# Moneybox.net
KiCad netlist of a schematic drawn in Altium Designer
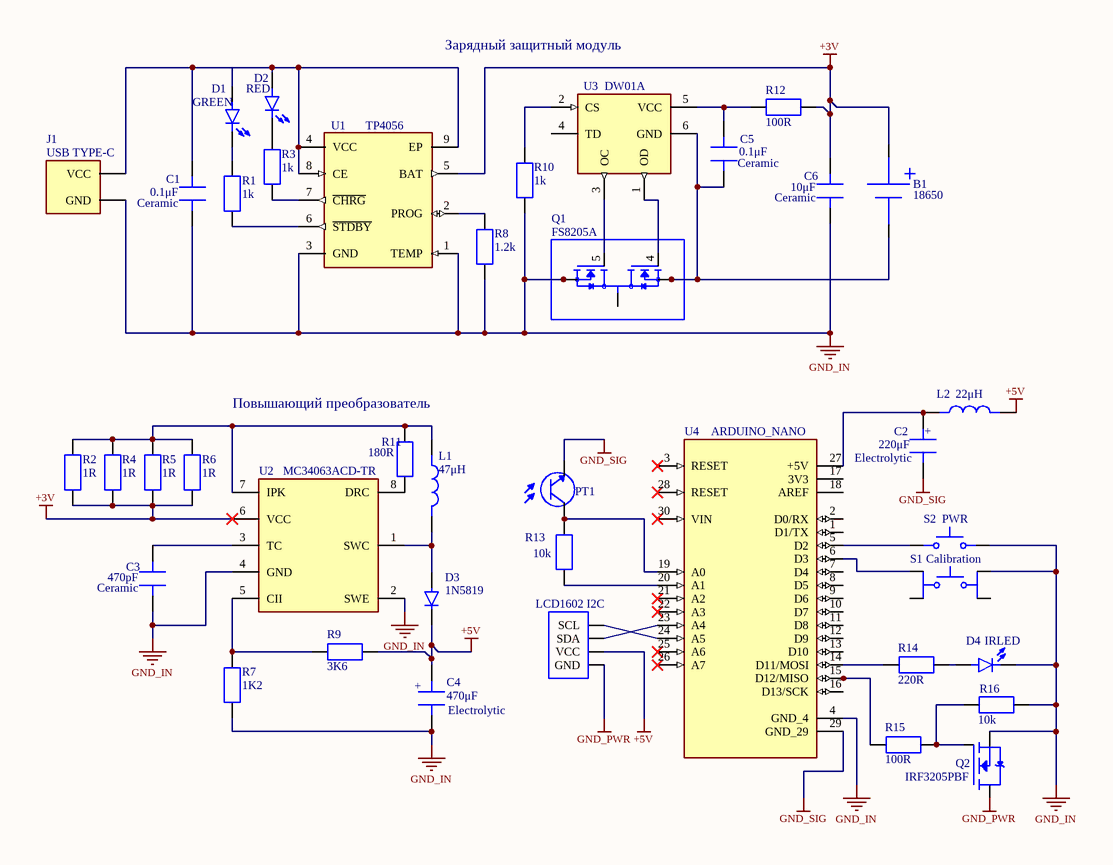
[diagram p0: Moneybox.SchDoc]

(export (version "E")
  (design (tool "Eeschema 10.0.6"))
  (components
    (comp (ref "B1") (value "18650") (footprint "18650 PLS 2") (libsource (lib "My") (part "Baterry 18650")))
    (comp (ref "C1")
      (value "0.1μF")
      (footprint "R1206")
      (fields (field (name "TYPES") "Ceramic") (field (name "Comment") "Capicator"))
      (libsource (lib "My") (part "Capicator"))
    )
    (comp (ref "C2")
      (value "220μF")
      (footprint "CAPICATOR Radial 6.3mm")
      (fields
        (field (name "POLARITY") "+")
        (field (name "TYPES") "Electrolytic")
        (field (name "Comment") "Capicator")
      )
      (libsource (lib "My") (part "Capicator"))
    )
    (comp (ref "C3")
      (value "470pF")
      (footprint "R1206")
      (fields (field (name "TYPES") "Ceramic") (field (name "Comment") "Capicator"))
      (libsource (lib "My") (part "Capicator"))
    )
    (comp (ref "C4")
      (value "470μF")
      (footprint "CAPICATOR Radial 6.3mm")
      (fields
        (field (name "POLARITY") "+")
        (field (name "TYPES") "Electrolytic")
        (field (name "Comment") "Capicator")
      )
      (libsource (lib "My") (part "Capicator"))
    )
    (comp (ref "C5")
      (value "0.1μF")
      (footprint "R1206")
      (fields (field (name "TYPES") "Ceramic") (field (name "Comment") "Capicator"))
      (libsource (lib "My") (part "Capicator"))
    )
    (comp (ref "C6")
      (value "10μF")
      (footprint "R1206")
      (fields (field (name "TYPES") "Ceramic") (field (name "Comment") "Capicator"))
      (libsource (lib "My") (part "Capicator"))
    )
    (comp (ref "D1")
      (value "GREEN")
      (footprint "LED_DIP")
      (description "infrared LED 850nm")
      (fields (field (name "MP") "WP7113ID") (field (name "MF") "Kingbright"))
      (libsource (lib "My") (part "IRLED"))
    )
    (comp (ref "D2")
      (value "RED")
      (footprint "LED_DIP")
      (description "infrared LED 850nm")
      (fields (field (name "MP") "WP7113ID") (field (name "MF") "Kingbright"))
      (libsource (lib "My") (part "IRLED"))
    )
    (comp (ref "D3")
      (value "1N5819")
      (footprint "DIOD 1N5819")
      (description "1A, 40V, Planar Schottky")
      (fields (field (name "MF") "Taiwan Semiconductor"))
      (libsource (lib "My") (part "1N5819"))
    )
    (comp (ref "D4")
      (value "IRLED")
      (footprint "IRLED_DIP")
      (description "infrared LED 850nm")
      (fields (field (name "MP") "WP7113ID") (field (name "MF") "Kingbright"))
      (libsource (lib "My") (part "IRLED"))
    )
    (comp (ref "J1")
      (value "USB Type C")
      (footprint "18650 PLS 2")
      (description "USB Type C, Power Only, Top mount, Center Height 1.68mm, Single Row, Surface Mount")
      (fields (field (name "MF") "Amphenol") (field (name "MP") "GSB1C411101DSHR"))
      (libsource (lib "My") (part "USB Type C"))
    )
    (comp (ref "L1")
      (value "47μH")
      (footprint "INDUCTOR THT")
      (description "Inductor THT axial")
      (fields (field (name "MF") "TDK Electronics") (field (name "MP") "B78108S1102K000"))
      (libsource (lib "My") (part "Inductor THT"))
    )
    (comp (ref "L2")
      (value "22μH")
      (footprint "INDUCTOR THT")
      (description "Inductor THT axial")
      (fields (field (name "MF") "TDK Electronics") (field (name "MP") "B78108S1102K000"))
      (libsource (lib "My") (part "Inductor THT"))
    )
    (comp (ref "LCD1") (value "LCD1602 I2C") (footprint "PLS-4") (libsource (lib "My") (part "LCD1602 I2C")))
    (comp (ref "PT1")
      (value "Phototransistors")
      (footprint "Phototransistors DIP")
      (description "Phototransistors 850nm Top View Radial")
      (fields (field (name "MF") "Vishay") (field (name "MP") "BPW85A"))
      (libsource (lib "My") (part "Phototransistors"))
    )
    (comp (ref "Q1")
      (value "FS8205A")
      (footprint "FS8205A")
      (fields (field (name "MF") "Fortune Semiconductor"))
      (libsource (lib "My") (part "FS8205A"))
    )
    (comp (ref "Q2")
      (value "IRF3205PBF")
      (footprint "MOSFET IRF3205PBF")
      (fields (field (name "MF") "Infineon Technologies"))
      (libsource (lib "My") (part "IRF3205PBF"))
    )
    (comp (ref "R1")
      (value "1k")
      (footprint "R1206")
      (fields (field (name "Comment") "Resistor 1206"))
      (libsource (lib "My") (part "R1206"))
    )
    (comp (ref "R2")
      (value "1R")
      (footprint "R1206")
      (fields (field (name "Comment") "Resistor 1206"))
      (libsource (lib "My") (part "R1206"))
    )
    (comp (ref "R3")
      (value "1k")
      (footprint "R1206")
      (fields (field (name "Comment") "Resistor 1206"))
      (libsource (lib "My") (part "R1206"))
    )
    (comp (ref "R4")
      (value "1R")
      (footprint "R1206")
      (fields (field (name "Comment") "Resistor 1206"))
      (libsource (lib "My") (part "R1206"))
    )
    (comp (ref "R5")
      (value "1R")
      (footprint "R1206")
      (fields (field (name "Comment") "Resistor 1206"))
      (libsource (lib "My") (part "R1206"))
    )
    (comp (ref "R6")
      (value "1R")
      (footprint "R1206")
      (fields (field (name "Comment") "Resistor 1206"))
      (libsource (lib "My") (part "R1206"))
    )
    (comp (ref "R7")
      (value "1K2")
      (footprint "R1206")
      (fields (field (name "Comment") "Resistor 1206"))
      (libsource (lib "My") (part "R1206"))
    )
    (comp (ref "R8")
      (value "1.2k")
      (footprint "R1206")
      (fields (field (name "Comment") "Resistor 1206"))
      (libsource (lib "My") (part "R1206"))
    )
    (comp (ref "R9")
      (value "3K6")
      (footprint "R1206")
      (fields (field (name "Comment") "Resistor 1206"))
      (libsource (lib "My") (part "R1206"))
    )
    (comp (ref "R10")
      (value "1k")
      (footprint "R1206")
      (fields (field (name "Comment") "Resistor 1206"))
      (libsource (lib "My") (part "R1206"))
    )
    (comp (ref "R11")
      (value "180R")
      (footprint "R1206")
      (fields (field (name "Comment") "Resistor 1206"))
      (libsource (lib "My") (part "R1206"))
    )
    (comp (ref "R12")
      (value "100R")
      (footprint "R1206")
      (fields (field (name "Comment") "Resistor 1206"))
      (libsource (lib "My") (part "R1206"))
    )
    (comp (ref "R13")
      (value "10k")
      (footprint "R1206")
      (fields (field (name "Comment") "Resistor 1206"))
      (libsource (lib "My") (part "R1206"))
    )
    (comp (ref "R14")
      (value "220R")
      (footprint "R1206")
      (fields (field (name "Comment") "Resistor 1206"))
      (libsource (lib "My") (part "R1206"))
    )
    (comp (ref "R15")
      (value "100R")
      (footprint "R1206")
      (fields (field (name "Comment") "Resistor 1206"))
      (libsource (lib "My") (part "R1206"))
    )
    (comp (ref "R16")
      (value "10k")
      (footprint "R1206")
      (fields (field (name "Comment") "Resistor 1206"))
      (libsource (lib "My") (part "R1206"))
    )
    (comp (ref "S1")
      (value "Сalibration")
      (footprint "Tactile Switch")
      (fields (field (name "MP") "TL1105AF160Q"))
      (libsource (lib "My") (part "Tactile Switch"))
    )
    (comp (ref "S2")
      (value "PWR")
      (footprint "PLS-2")
      (fields (field (name "MP") "TL1105AF160Q"))
      (libsource (lib "My") (part "Switch PLS-2"))
    )
    (comp (ref "U1")
      (value "TP4056")
      (footprint "TP4056")
      (description "Complete single cell Li-Ion battery with a constant current / constant voltage linear charger")
      (fields (field (name "MF") "NanJing Top Power ASIC Corp."))
      (libsource (lib "My") (part "TP4056"))
    )
    (comp (ref "U2")
      (value "MC34063ACD-TR")
      (footprint "MC34063ACD-TR_SOIC8")
      (fields (field (name "MF") "STMicroelectronics"))
      (libsource (lib "My") (part "MC34063ACD-TR"))
    )
    (comp (ref "U3")
      (value "DW01A")
      (footprint "DW01A")
      (description "One Cell Lithium-ion/Polymer Battery Protection IC")
      (fields (field (name "MF") "Fortune Semiconductor"))
      (libsource (lib "My") (part "DW01A"))
    )
    (comp (ref "U4")
      (value "ARDUINO_NANO")
      (footprint "ARDUINO_NANO")
      (description "ATmega328 Arduino Nano")
      (fields (field (name "MF") "Arduino") (field (name "MP") "Arduino Nano"))
      (libsource (lib "My") (part "ARDUINO_NANO"))
    )
  )
  (nets
    (net (code "1") (name "+3V") (class "Default")
      (node (ref "B1") (pin "1") (pinfunction "1_1") (pintype "passive"))
      (node (ref "C6") (pin "2") (pinfunction "2_2") (pintype "passive"))
      (node (ref "R12") (pin "2") (pinfunction "1_2") (pintype "passive"))
      (node (ref "R2") (pin "1") (pinfunction "0_1") (pintype "passive"))
      (node (ref "R4") (pin "1") (pinfunction "0_1") (pintype "passive"))
      (node (ref "R5") (pin "1") (pinfunction "0_1") (pintype "passive"))
      (node (ref "R6") (pin "1") (pinfunction "0_1") (pintype "passive"))
      (node (ref "U1") (pin "5") (pinfunction "BAT_5") (pintype "output"))
      (node (ref "U2") (pin "6") (pinfunction "VCC_6") (pintype "power_in"))
    )
    (net (code "2") (name "+5V") (class "Default")
      (node (ref "C4") (pin "1") (pinfunction "1_1") (pintype "passive"))
      (node (ref "D3") (pin "2") (pinfunction "2_2") (pintype "passive"))
      (node (ref "L2") (pin "2") (pinfunction "2_2") (pintype "passive"))
      (node (ref "LCD1") (pin "2") (pinfunction "VCC_2") (pintype "bidirectional"))
      (node (ref "R9") (pin "1") (pinfunction "0_1") (pintype "passive"))
    )
    (net (code "3") (name "GND_IN") (class "Default")
      (node (ref "C1") (pin "1") (pinfunction "1_1") (pintype "passive"))
      (node (ref "C3") (pin "1") (pinfunction "1_1") (pintype "passive"))
      (node (ref "C4") (pin "2") (pinfunction "2_2") (pintype "passive"))
      (node (ref "C6") (pin "1") (pinfunction "1_1") (pintype "passive"))
      (node (ref "D4") (pin "2") (pinfunction "2_2") (pintype "passive"))
      (node (ref "J1") (pin "2") (pinfunction "GND_2") (pintype "power_in"))
      (node (ref "Q1") (pin "6") (pinfunction "S2_6") (pintype "passive"))
      (node (ref "Q1") (pin "7") (pinfunction "S2_7") (pintype "passive"))
      (node (ref "Q2") (pin "3") (pinfunction "S_3") (pintype "passive"))
      (node (ref "R10") (pin "2") (pinfunction "1_2") (pintype "passive"))
      (node (ref "R16") (pin "2") (pinfunction "1_2") (pintype "passive"))
      (node (ref "R7") (pin "1") (pinfunction "0_1") (pintype "passive"))
      (node (ref "R8") (pin "2") (pinfunction "1_2") (pintype "passive"))
      (node (ref "S1") (pin "3") (pinfunction "3_3") (pintype "passive"))
      (node (ref "S2") (pin "2") (pinfunction "2_2") (pintype "passive"))
      (node (ref "U1") (pin "1") (pinfunction "TEMP_1") (pintype "input"))
      (node (ref "U1") (pin "3") (pinfunction "GND_3") (pintype "power_in"))
      (node (ref "U2") (pin "2") (pinfunction "SWE_2") (pintype "passive"))
      (node (ref "U2") (pin "4") (pinfunction "GND_4") (pintype "passive"))
      (node (ref "U4") (pin "4") (pinfunction "GND_4_4") (pintype "power_in"))
    )
    (net (code "4") (name "GND_PWR") (class "Default")
      (node (ref "LCD1") (pin "1") (pinfunction "GND_1") (pintype "bidirectional"))
      (node (ref "Q2") (pin "2") (pinfunction "D_2") (pintype "passive"))
    )
    (net (code "5") (name "GND_SIG") (class "Default")
      (node (ref "C2") (pin "2") (pinfunction "2_2") (pintype "passive"))
      (node (ref "PT1") (pin "2") (pinfunction "2_2") (pintype "passive"))
      (node (ref "U4") (pin "29") (pinfunction "GND_29_29") (pintype "power_in"))
    )
    (net (code "6") (name "Net-(J1-VCC)") (class "Default")
      (node (ref "C1") (pin "2") (pinfunction "2_2") (pintype "passive"))
      (node (ref "D1") (pin "1") (pinfunction "1_1") (pintype "passive"))
      (node (ref "D2") (pin "1") (pinfunction "1_1") (pintype "passive"))
      (node (ref "J1") (pin "1") (pinfunction "VCC_1") (pintype "power_in"))
      (node (ref "U1") (pin "4") (pinfunction "VCC_4") (pintype "power_in"))
      (node (ref "U1") (pin "8") (pinfunction "CE_8") (pintype "input"))
      (node (ref "U1") (pin "9") (pinfunction "EP_9") (pintype "passive"))
    )
    (net (code "7") (name "Net-(LCD1-SCL)") (class "Default")
      (node (ref "LCD1") (pin "4") (pinfunction "SCL_4") (pintype "bidirectional"))
      (node (ref "U4") (pin "24") (pinfunction "A5_24") (pintype "input"))
    )
    (net (code "8") (name "Net-(LCD1-SDA)") (class "Default")
      (node (ref "LCD1") (pin "3") (pinfunction "SDA_3") (pintype "bidirectional"))
      (node (ref "U4") (pin "23") (pinfunction "A4_23") (pintype "input"))
    )
    (net (code "9") (name "Net-(Q1-D12-Pad1)") (class "Default")
      (node (ref "Q1") (pin "1") (pinfunction "D12_1") (pintype "passive"))
      (node (ref "Q1") (pin "8") (pinfunction "D12_8") (pintype "passive"))
    )
    (net (code "10") (name "Net-(Q1-G1)") (class "Default")
      (node (ref "Q1") (pin "4") (pinfunction "G1_4") (pintype "passive"))
      (node (ref "U3") (pin "1") (pinfunction "OD_1") (pintype "output"))
    )
    (net (code "11") (name "Net-(Q1-G2)") (class "Default")
      (node (ref "Q1") (pin "5") (pinfunction "G2_5") (pintype "passive"))
      (node (ref "U3") (pin "3") (pinfunction "OC_3") (pintype "output"))
    )
    (net (code "12") (name "Net-(Q2-G)") (class "Default")
      (node (ref "Q2") (pin "1") (pinfunction "G_1") (pintype "passive"))
      (node (ref "R15") (pin "2") (pinfunction "1_2") (pintype "passive"))
      (node (ref "R16") (pin "1") (pinfunction "0_1") (pintype "passive"))
    )
    (net (code "13") (name "Net-(R1-0)") (class "Default")
      (node (ref "D1") (pin "2") (pinfunction "2_2") (pintype "passive"))
      (node (ref "R1") (pin "1") (pinfunction "0_1") (pintype "passive"))
    )
    (net (code "14") (name "Net-(R1-1)") (class "Default")
      (node (ref "R1") (pin "2") (pinfunction "1_2") (pintype "passive"))
      (node (ref "U1") (pin "6") (pinfunction "~{STDBY}_6") (pintype "output"))
    )
    (net (code "15") (name "Net-(R3-0)") (class "Default")
      (node (ref "D2") (pin "2") (pinfunction "2_2") (pintype "passive"))
      (node (ref "R3") (pin "1") (pinfunction "0_1") (pintype "passive"))
    )
    (net (code "16") (name "Net-(R3-1)") (class "Default")
      (node (ref "R3") (pin "2") (pinfunction "1_2") (pintype "passive"))
      (node (ref "U1") (pin "7") (pinfunction "~{CHRG}_7") (pintype "output"))
    )
    (net (code "17") (name "Net-(R7-1)") (class "Default")
      (node (ref "R7") (pin "2") (pinfunction "1_2") (pintype "passive"))
      (node (ref "R9") (pin "2") (pinfunction "1_2") (pintype "passive"))
      (node (ref "U2") (pin "5") (pinfunction "CII_5") (pintype "passive"))
    )
    (net (code "18") (name "Net-(R8-0)") (class "Default")
      (node (ref "R8") (pin "1") (pinfunction "0_1") (pintype "passive"))
      (node (ref "U1") (pin "2") (pinfunction "PROG_2") (pintype "bidirectional"))
    )
    (net (code "19") (name "Net-(R10-0)") (class "Default")
      (node (ref "R10") (pin "1") (pinfunction "0_1") (pintype "passive"))
      (node (ref "U3") (pin "2") (pinfunction "CS_2") (pintype "input"))
    )
    (net (code "20") (name "Net-(R11-0)") (class "Default")
      (node (ref "R11") (pin "1") (pinfunction "0_1") (pintype "passive"))
      (node (ref "U2") (pin "8") (pinfunction "DRC_8") (pintype "passive"))
    )
    (net (code "21") (name "Net-(R11-1)") (class "Default")
      (node (ref "L1") (pin "1") (pinfunction "1_1") (pintype "passive"))
      (node (ref "R11") (pin "2") (pinfunction "1_2") (pintype "passive"))
      (node (ref "R2") (pin "2") (pinfunction "1_2") (pintype "passive"))
      (node (ref "R4") (pin "2") (pinfunction "1_2") (pintype "passive"))
      (node (ref "R5") (pin "2") (pinfunction "1_2") (pintype "passive"))
      (node (ref "R6") (pin "2") (pinfunction "1_2") (pintype "passive"))
      (node (ref "U2") (pin "7") (pinfunction "IPK_7") (pintype "passive"))
    )
    (net (code "22") (name "Net-(R12-0)") (class "Default")
      (node (ref "C5") (pin "2") (pinfunction "2_2") (pintype "passive"))
      (node (ref "R12") (pin "1") (pinfunction "0_1") (pintype "passive"))
      (node (ref "U3") (pin "5") (pinfunction "VCC_5") (pintype "power_in"))
    )
    (net (code "23") (name "Net-(R13-0)") (class "Default")
      (node (ref "R13") (pin "1") (pinfunction "0_1") (pintype "passive"))
      (node (ref "U4") (pin "20") (pinfunction "A1_20") (pintype "input"))
    )
    (net (code "24") (name "Net-(R13-1)") (class "Default")
      (node (ref "PT1") (pin "1") (pinfunction "1_1") (pintype "passive"))
      (node (ref "R13") (pin "2") (pinfunction "1_2") (pintype "passive"))
      (node (ref "U4") (pin "19") (pinfunction "A0_19") (pintype "input"))
    )
    (net (code "25") (name "Net-(R14-0)") (class "Default")
      (node (ref "R14") (pin "1") (pinfunction "0_1") (pintype "passive"))
      (node (ref "U4") (pin "14") (pinfunction "D11/MOSI_14") (pintype "bidirectional"))
    )
    (net (code "26") (name "Net-(R14-1)") (class "Default")
      (node (ref "D4") (pin "1") (pinfunction "1_1") (pintype "passive"))
      (node (ref "R14") (pin "2") (pinfunction "1_2") (pintype "passive"))
    )
    (net (code "27") (name "Net-(R15-0)") (class "Default")
      (node (ref "R15") (pin "1") (pinfunction "0_1") (pintype "passive"))
      (node (ref "U4") (pin "15") (pinfunction "D12/MISO_15") (pintype "bidirectional"))
    )
    (net (code "28") (name "Net-(U2-SWC)") (class "Default")
      (node (ref "D3") (pin "1") (pinfunction "1_1") (pintype "passive"))
      (node (ref "L1") (pin "2") (pinfunction "2_2") (pintype "passive"))
      (node (ref "U2") (pin "1") (pinfunction "SWC_1") (pintype "passive"))
    )
    (net (code "29") (name "Net-(U2-TC)") (class "Default")
      (node (ref "C3") (pin "2") (pinfunction "2_2") (pintype "passive"))
      (node (ref "U2") (pin "3") (pinfunction "TC_3") (pintype "passive"))
    )
    (net (code "30") (name "Net-(U3-GND)") (class "Default")
      (node (ref "B1") (pin "2") (pinfunction "2_2") (pintype "passive"))
      (node (ref "C5") (pin "1") (pinfunction "1_1") (pintype "passive"))
      (node (ref "Q1") (pin "2") (pinfunction "S1_2") (pintype "passive"))
      (node (ref "Q1") (pin "3") (pinfunction "S1_3") (pintype "passive"))
      (node (ref "U3") (pin "6") (pinfunction "GND_6") (pintype "power_in"))
    )
    (net (code "31") (name "Net-(U4-+5V)") (class "Default")
      (node (ref "C2") (pin "1") (pinfunction "1_1") (pintype "passive"))
      (node (ref "L2") (pin "1") (pinfunction "1_1") (pintype "passive"))
      (node (ref "U4") (pin "27") (pinfunction "+5V_27") (pintype "power_in"))
    )
    (net (code "32") (name "Net-(U4-D2)") (class "Default")
      (node (ref "S2") (pin "1") (pinfunction "1_1") (pintype "passive"))
      (node (ref "U4") (pin "5") (pinfunction "D2_5") (pintype "bidirectional"))
    )
    (net (code "33") (name "Net-(U4-D3)") (class "Default")
      (node (ref "S1") (pin "1") (pinfunction "1_1") (pintype "passive"))
      (node (ref "U4") (pin "6") (pinfunction "D3_6") (pintype "bidirectional"))
    )
    (net (code "34") (name "unconnected-(S1-Pad2)") (class "Default")
      (node (ref "S1") (pin "2") (pinfunction "2_2") (pintype "passive"))
    )
    (net (code "35") (name "unconnected-(S1-Pad4)") (class "Default")
      (node (ref "S1") (pin "4") (pinfunction "4_4") (pintype "passive"))
    )
    (net (code "36") (name "unconnected-(U3-TD-Pad4)") (class "Default")
      (node (ref "U3") (pin "4") (pinfunction "TD_4") (pintype "passive"))
    )
    (net (code "37") (name "unconnected-(U4-3V3-Pad17)") (class "Default")
      (node (ref "U4") (pin "17") (pinfunction "3V3_17") (pintype "power_in"))
    )
    (net (code "38") (name "unconnected-(U4-A2-Pad21)") (class "Default")
      (node (ref "U4") (pin "21") (pinfunction "A2_21") (pintype "input+no_connect"))
    )
    (net (code "39") (name "unconnected-(U4-A3-Pad22)") (class "Default")
      (node (ref "U4") (pin "22") (pinfunction "A3_22") (pintype "input+no_connect"))
    )
    (net (code "40") (name "unconnected-(U4-A6-Pad25)") (class "Default")
      (node (ref "U4") (pin "25") (pinfunction "A6_25") (pintype "input+no_connect"))
    )
    (net (code "41") (name "unconnected-(U4-A7-Pad26)") (class "Default")
      (node (ref "U4") (pin "26") (pinfunction "A7_26") (pintype "input+no_connect"))
    )
    (net (code "42") (name "unconnected-(U4-AREF-Pad18)") (class "Default")
      (node (ref "U4") (pin "18") (pinfunction "AREF_18") (pintype "power_in"))
    )
    (net (code "43") (name "unconnected-(U4-D0{slash}RX-Pad2)") (class "Default")
      (node (ref "U4") (pin "2") (pinfunction "D0/RX_2") (pintype "bidirectional"))
    )
    (net (code "44") (name "unconnected-(U4-D1{slash}TX-Pad1)") (class "Default")
      (node (ref "U4") (pin "1") (pinfunction "D1/TX_1") (pintype "bidirectional"))
    )
    (net (code "45") (name "unconnected-(U4-D4-Pad7)") (class "Default")
      (node (ref "U4") (pin "7") (pinfunction "D4_7") (pintype "bidirectional"))
    )
    (net (code "46") (name "unconnected-(U4-D5-Pad8)") (class "Default")
      (node (ref "U4") (pin "8") (pinfunction "D5_8") (pintype "bidirectional"))
    )
    (net (code "47") (name "unconnected-(U4-D6-Pad9)") (class "Default")
      (node (ref "U4") (pin "9") (pinfunction "D6_9") (pintype "bidirectional"))
    )
    (net (code "48") (name "unconnected-(U4-D7-Pad10)") (class "Default")
      (node (ref "U4") (pin "10") (pinfunction "D7_10") (pintype "bidirectional"))
    )
    (net (code "49") (name "unconnected-(U4-D8-Pad11)") (class "Default")
      (node (ref "U4") (pin "11") (pinfunction "D8_11") (pintype "bidirectional"))
    )
    (net (code "50") (name "unconnected-(U4-D9-Pad12)") (class "Default")
      (node (ref "U4") (pin "12") (pinfunction "D9_12") (pintype "bidirectional"))
    )
    (net (code "51") (name "unconnected-(U4-D10-Pad13)") (class "Default")
      (node (ref "U4") (pin "13") (pinfunction "D10_13") (pintype "bidirectional"))
    )
    (net (code "52") (name "unconnected-(U4-D13{slash}SCK-Pad16)") (class "Default")
      (node (ref "U4") (pin "16") (pinfunction "D13/SCK_16") (pintype "bidirectional"))
    )
    (net (code "53") (name "unconnected-(U4-RESET-Pad3)") (class "Default")
      (node (ref "U4") (pin "3") (pinfunction "RESET_3") (pintype "input+no_connect"))
    )
    (net (code "54") (name "unconnected-(U4-RESET-Pad28)") (class "Default")
      (node (ref "U4") (pin "28") (pinfunction "RESET_28") (pintype "input+no_connect"))
    )
    (net (code "55") (name "unconnected-(U4-VIN-Pad30)") (class "Default")
      (node (ref "U4") (pin "30") (pinfunction "VIN_30") (pintype "input+no_connect"))
    )
  )
)
